# conexion_sensor_hall.net
KiCad netlist of a schematic drawn in Altium Designer
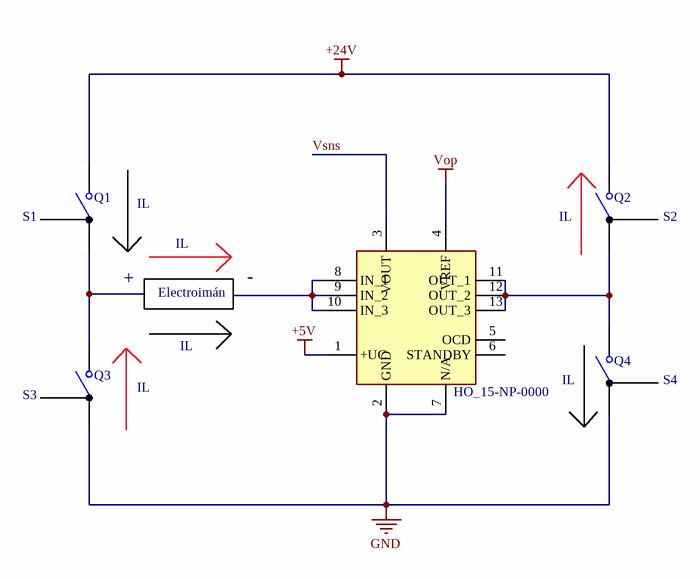
[diagram p0: conexion_sensor_hall.SchDoc]

(export (version "E")
  (design (tool "Eeschema 10.0.6"))
  (components
    (comp (ref "Q1")
      (value "SW-SPST")
      (footprint "SPST-2")
      (description "Single-Pole, Single-Throw Switch")
      (fields (field (name "PUBLISHER") "Altium Limited"))
      (libsource (lib "Miscellaneous Devices") (part "SW-SPST"))
    )
    (comp (ref "Q2")
      (value "SW-SPST")
      (footprint "SPST-2")
      (description "Single-Pole, Single-Throw Switch")
      (fields (field (name "PUBLISHER") "Altium Limited"))
      (libsource (lib "Miscellaneous Devices") (part "SW-SPST"))
    )
    (comp (ref "Q3")
      (value "SW-SPST")
      (footprint "SPST-2")
      (description "Single-Pole, Single-Throw Switch")
      (fields (field (name "PUBLISHER") "Altium Limited"))
      (libsource (lib "Miscellaneous Devices") (part "SW-SPST"))
    )
    (comp (ref "Q4")
      (value "SW-SPST")
      (footprint "SPST-2")
      (description "Single-Pole, Single-Throw Switch")
      (fields (field (name "PUBLISHER") "Altium Limited"))
      (libsource (lib "Miscellaneous Devices") (part "SW-SPST"))
    )
    (comp (ref "U103")
      (value "HO_15-NP-0000")
      (footprint "HO15NP0000")
      (description "SENSOR CURRENT HALL 15A AC/DC")
      (fields (field (name "MANUFACTURER") "LEM USA Inc."))
      (libsource (lib "Levitador_GMI") (part "HO_15-NP-0000"))
    )
  )
  (nets
    (net (code "1") (name "+5V") (class "Default")
      (node (ref "U103") (pin "1") (pinfunction "+UC_1") (pintype "passive"))
    )
    (net (code "2") (name "+24V") (class "Default")
      (node (ref "Q1") (pin "2") (pinfunction "NO_2") (pintype "passive"))
      (node (ref "Q2") (pin "2") (pinfunction "NO_2") (pintype "passive"))
    )
    (net (code "3") (name "/Vsns") (class "Default")
      (node (ref "U103") (pin "3") (pinfunction "VOUT_3") (pintype "passive"))
    )
    (net (code "4") (name "GND") (class "Default")
      (node (ref "Q3") (pin "1") (pinfunction "COMMON_1") (pintype "passive"))
      (node (ref "Q4") (pin "1") (pinfunction "COMMON_1") (pintype "passive"))
      (node (ref "U103") (pin "2") (pinfunction "GND_2") (pintype "passive"))
      (node (ref "U103") (pin "7") (pinfunction "N/A_7") (pintype "passive"))
    )
    (net (code "5") (name "Net-(Q1-COMMON)") (class "Default")
      (node (ref "Q1") (pin "1") (pinfunction "COMMON_1") (pintype "passive"))
      (node (ref "Q3") (pin "2") (pinfunction "NO_2") (pintype "passive"))
    )
    (net (code "6") (name "Net-(Q2-COMMON)") (class "Default")
      (node (ref "Q2") (pin "1") (pinfunction "COMMON_1") (pintype "passive"))
      (node (ref "Q4") (pin "2") (pinfunction "NO_2") (pintype "passive"))
      (node (ref "U103") (pin "11") (pinfunction "OUT_1_11") (pintype "passive"))
      (node (ref "U103") (pin "12") (pinfunction "OUT_2_12") (pintype "passive"))
      (node (ref "U103") (pin "13") (pinfunction "OUT_3_13") (pintype "passive"))
    )
    (net (code "7") (name "Net-(U103-IN_1)") (class "Default")
      (node (ref "U103") (pin "10") (pinfunction "IN_3_10") (pintype "passive"))
      (node (ref "U103") (pin "8") (pinfunction "IN_1_8") (pintype "passive"))
      (node (ref "U103") (pin "9") (pinfunction "IN_2_9") (pintype "passive"))
    )
    (net (code "8") (name "Vop") (class "Default")
      (node (ref "U103") (pin "4") (pinfunction "VREF_4") (pintype "passive"))
    )
    (net (code "9") (name "unconnected-(U103-OCD-Pad5)") (class "Default")
      (node (ref "U103") (pin "5") (pinfunction "OCD_5") (pintype "passive"))
    )
    (net (code "10") (name "unconnected-(U103-STANDBY-Pad6)") (class "Default")
      (node (ref "U103") (pin "6") (pinfunction "STANDBY_6") (pintype "passive"))
    )
  )
)
